# zxld400-9-leds-mk-2-leds.net
KiCad netlist of a schematic drawn in EAGLE
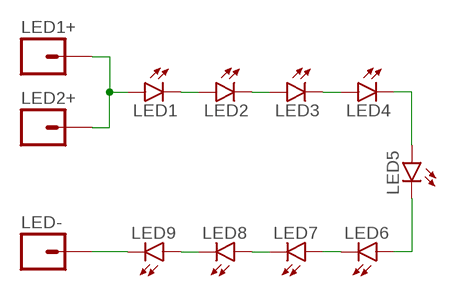
[diagram p0: schematic, sheet 1]

(export (version "E")
  (design (tool "Eeschema 10.0.6"))
  (components
    (comp (ref "LED-")
      (value "M01PTH")
      (footprint "eagle-import:1X01")
      (libsource (lib "eagle-import") (part "M01PTH"))
    )
    (comp (ref "LED1")
      (value "LED5MM_SHORTPADS")
      (footprint "eagle-import:LED5MM_SHORTPADS")
      (libsource (lib "eagle-import") (part "LED5MM_SHORTPADS"))
    )
    (comp (ref "LED1+")
      (value "M01PTH")
      (footprint "eagle-import:1X01")
      (libsource (lib "eagle-import") (part "M01PTH"))
    )
    (comp (ref "LED2")
      (value "LED5MM_SHORTPADS")
      (footprint "eagle-import:LED5MM_SHORTPADS")
      (libsource (lib "eagle-import") (part "LED5MM_SHORTPADS"))
    )
    (comp (ref "LED2+")
      (value "M01PTH")
      (footprint "eagle-import:1X01")
      (libsource (lib "eagle-import") (part "M01PTH"))
    )
    (comp (ref "LED3")
      (value "LED5MM_SHORTPADS")
      (footprint "eagle-import:LED5MM_SHORTPADS")
      (libsource (lib "eagle-import") (part "LED5MM_SHORTPADS"))
    )
    (comp (ref "LED4")
      (value "LED5MM_SHORTPADS")
      (footprint "eagle-import:LED5MM_SHORTPADS")
      (libsource (lib "eagle-import") (part "LED5MM_SHORTPADS"))
    )
    (comp (ref "LED5")
      (value "LED5MM_SHORTPADS")
      (footprint "eagle-import:LED5MM_SHORTPADS")
      (libsource (lib "eagle-import") (part "LED5MM_SHORTPADS"))
    )
    (comp (ref "LED6")
      (value "LED5MM_SHORTPADS")
      (footprint "eagle-import:LED5MM_SHORTPADS")
      (libsource (lib "eagle-import") (part "LED5MM_SHORTPADS"))
    )
    (comp (ref "LED7")
      (value "LED5MM_SHORTPADS")
      (footprint "eagle-import:LED5MM_SHORTPADS")
      (libsource (lib "eagle-import") (part "LED5MM_SHORTPADS"))
    )
    (comp (ref "LED8")
      (value "LED5MM_SHORTPADS")
      (footprint "eagle-import:LED5MM_SHORTPADS")
      (libsource (lib "eagle-import") (part "LED5MM_SHORTPADS"))
    )
    (comp (ref "LED9")
      (value "LED5MM_SHORTPADS")
      (footprint "eagle-import:LED5MM_SHORTPADS")
      (libsource (lib "eagle-import") (part "LED5MM_SHORTPADS"))
    )
  )
  (nets
    (net (code "1") (name "Net-(LED1+-Pad1)") (class "Default")
      (node (ref "LED1") (pin "A") (pinfunction "A_A") (pintype "passive"))
      (node (ref "LED1+") (pin "1") (pinfunction "1_1") (pintype "passive"))
      (node (ref "LED2+") (pin "1") (pinfunction "1_1") (pintype "passive"))
    )
    (net (code "2") (name "Net-(LED1-C)") (class "Default")
      (node (ref "LED1") (pin "K") (pinfunction "C_K") (pintype "passive"))
      (node (ref "LED2") (pin "A") (pinfunction "A_A") (pintype "passive"))
    )
    (net (code "3") (name "Net-(LED2-C)") (class "Default")
      (node (ref "LED2") (pin "K") (pinfunction "C_K") (pintype "passive"))
      (node (ref "LED3") (pin "A") (pinfunction "A_A") (pintype "passive"))
    )
    (net (code "4") (name "Net-(LED3-C)") (class "Default")
      (node (ref "LED3") (pin "K") (pinfunction "C_K") (pintype "passive"))
      (node (ref "LED4") (pin "A") (pinfunction "A_A") (pintype "passive"))
    )
    (net (code "5") (name "Net-(LED4-C)") (class "Default")
      (node (ref "LED4") (pin "K") (pinfunction "C_K") (pintype "passive"))
      (node (ref "LED5") (pin "A") (pinfunction "A_A") (pintype "passive"))
    )
    (net (code "6") (name "Net-(LED5-C)") (class "Default")
      (node (ref "LED5") (pin "K") (pinfunction "C_K") (pintype "passive"))
      (node (ref "LED6") (pin "A") (pinfunction "A_A") (pintype "passive"))
    )
    (net (code "7") (name "Net-(LED6-C)") (class "Default")
      (node (ref "LED6") (pin "K") (pinfunction "C_K") (pintype "passive"))
      (node (ref "LED7") (pin "A") (pinfunction "A_A") (pintype "passive"))
    )
    (net (code "8") (name "Net-(LED7-C)") (class "Default")
      (node (ref "LED7") (pin "K") (pinfunction "C_K") (pintype "passive"))
      (node (ref "LED8") (pin "A") (pinfunction "A_A") (pintype "passive"))
    )
    (net (code "9") (name "Net-(LED8-C)") (class "Default")
      (node (ref "LED8") (pin "K") (pinfunction "C_K") (pintype "passive"))
      (node (ref "LED9") (pin "A") (pinfunction "A_A") (pintype "passive"))
    )
    (net (code "10") (name "Net-(LED9-C)") (class "Default")
      (node (ref "LED-") (pin "1") (pinfunction "1_1") (pintype "passive"))
      (node (ref "LED9") (pin "K") (pinfunction "C_K") (pintype "passive"))
    )
  )
)
